# Ignition_Injection_Breakaway.net
KiCad netlist of a schematic drawn in Altium Designer
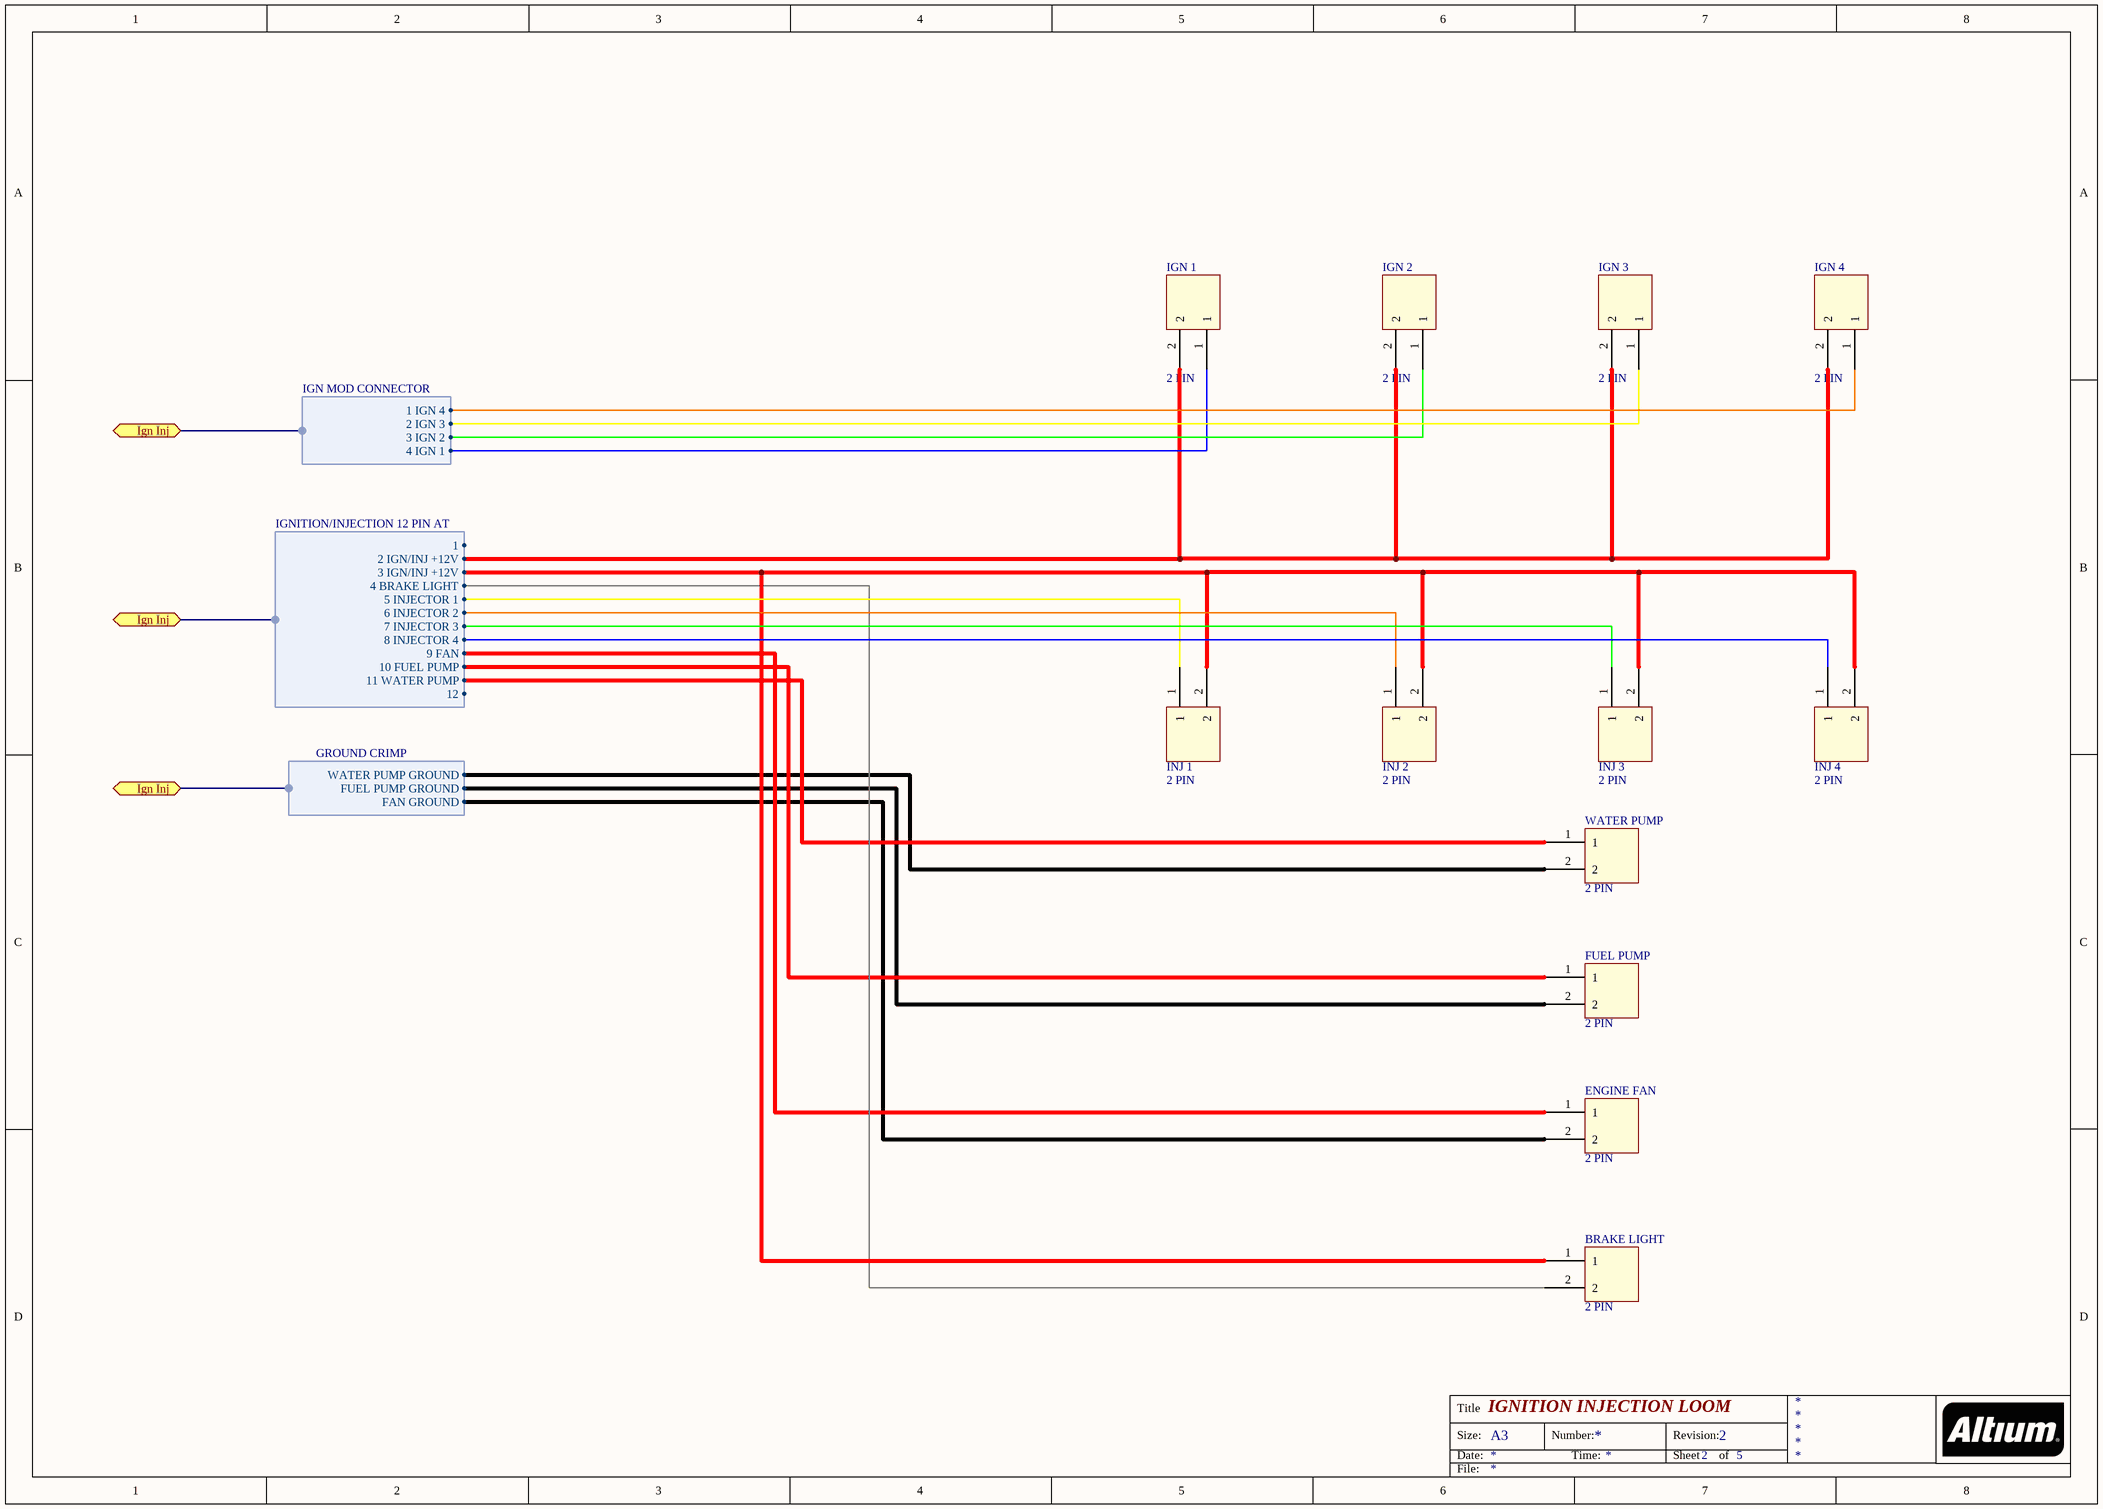
[diagram p0: Ignition Injection Breakaway.SchDoc]

(export (version "E")
  (design (tool "Eeschema 10.0.6"))
  (components
    (comp (ref "BRAKE LIGHT") (value "2 PIN") (libsource (lib "Loom Connectors") (part "2 PIN")))
    (comp (ref "ENGINE FAN") (value "2 PIN") (libsource (lib "Loom Connectors") (part "2 PIN")))
    (comp (ref "FUEL PUMP") (value "2 PIN") (libsource (lib "Loom Connectors") (part "2 PIN")))
    (comp (ref "IGN 1") (value "2 PIN") (libsource (lib "Loom Connectors") (part "2 PIN")))
    (comp (ref "IGN 2") (value "2 PIN") (libsource (lib "Loom Connectors") (part "2 PIN")))
    (comp (ref "IGN 3") (value "2 PIN") (libsource (lib "Loom Connectors") (part "2 PIN")))
    (comp (ref "IGN 4") (value "2 PIN") (libsource (lib "Loom Connectors") (part "2 PIN")))
    (comp (ref "INJ 1") (value "2 PIN") (libsource (lib "") (part "2 PIN_1")))
    (comp (ref "INJ 2") (value "2 PIN") (libsource (lib "") (part "2 PIN_1")))
    (comp (ref "INJ 3") (value "2 PIN") (libsource (lib "") (part "2 PIN_1")))
    (comp (ref "INJ 4") (value "2 PIN") (libsource (lib "") (part "2 PIN_1")))
    (comp (ref "WATER PUMP") (value "2 PIN") (libsource (lib "Loom Connectors") (part "2 PIN")))
  )
  (nets
    (net (code "2") (name "Net-(BRAKE LIGHT-Pad1)") (class "Default")
      (node (ref "BRAKE LIGHT") (pin "1") (pinfunction "1_1") (pintype "passive"))
      (node (ref "INJ 1") (pin "2") (pinfunction "2_2") (pintype "passive"))
      (node (ref "INJ 2") (pin "2") (pinfunction "2_2") (pintype "passive"))
      (node (ref "INJ 3") (pin "2") (pinfunction "2_2") (pintype "passive"))
      (node (ref "INJ 4") (pin "2") (pinfunction "2_2") (pintype "passive"))
    )
    (net (code "3") (name "Net-(IGN 1-Pad2)") (class "Default")
      (node (ref "IGN 1") (pin "2") (pinfunction "2_2") (pintype "passive"))
      (node (ref "IGN 2") (pin "2") (pinfunction "2_2") (pintype "passive"))
      (node (ref "IGN 3") (pin "2") (pinfunction "2_2") (pintype "passive"))
      (node (ref "IGN 4") (pin "2") (pinfunction "2_2") (pintype "passive"))
    )
    (net (code "4") (name "unconnected-(BRAKE LIGHT-Pad2)") (class "Default")
      (node (ref "BRAKE LIGHT") (pin "2") (pinfunction "2_2") (pintype "passive"))
    )
    (net (code "5") (name "unconnected-(ENGINE FAN-Pad1)") (class "Default")
      (node (ref "ENGINE FAN") (pin "1") (pinfunction "1_1") (pintype "passive"))
    )
    (net (code "6") (name "unconnected-(ENGINE FAN-Pad2)") (class "Default")
      (node (ref "ENGINE FAN") (pin "2") (pinfunction "2_2") (pintype "passive"))
    )
    (net (code "7") (name "unconnected-(FUEL PUMP-Pad1)") (class "Default")
      (node (ref "FUEL PUMP") (pin "1") (pinfunction "1_1") (pintype "passive"))
    )
    (net (code "8") (name "unconnected-(FUEL PUMP-Pad2)") (class "Default")
      (node (ref "FUEL PUMP") (pin "2") (pinfunction "2_2") (pintype "passive"))
    )
    (net (code "9") (name "unconnected-(IGN 1-Pad1)") (class "Default")
      (node (ref "IGN 1") (pin "1") (pinfunction "1_1") (pintype "passive"))
    )
    (net (code "10") (name "unconnected-(IGN 2-Pad1)") (class "Default")
      (node (ref "IGN 2") (pin "1") (pinfunction "1_1") (pintype "passive"))
    )
    (net (code "11") (name "unconnected-(IGN 3-Pad1)") (class "Default")
      (node (ref "IGN 3") (pin "1") (pinfunction "1_1") (pintype "passive"))
    )
    (net (code "12") (name "unconnected-(IGN 4-Pad1)") (class "Default")
      (node (ref "IGN 4") (pin "1") (pinfunction "1_1") (pintype "passive"))
    )
    (net (code "13") (name "unconnected-(INJ 1-Pad1)") (class "Default")
      (node (ref "INJ 1") (pin "1") (pinfunction "1_1") (pintype "passive"))
    )
    (net (code "14") (name "unconnected-(INJ 2-Pad1)") (class "Default")
      (node (ref "INJ 2") (pin "1") (pinfunction "1_1") (pintype "passive"))
    )
    (net (code "15") (name "unconnected-(INJ 3-Pad1)") (class "Default")
      (node (ref "INJ 3") (pin "1") (pinfunction "1_1") (pintype "passive"))
    )
    (net (code "16") (name "unconnected-(INJ 4-Pad1)") (class "Default")
      (node (ref "INJ 4") (pin "1") (pinfunction "1_1") (pintype "passive"))
    )
    (net (code "17") (name "unconnected-(WATER PUMP-Pad1)") (class "Default")
      (node (ref "WATER PUMP") (pin "1") (pinfunction "1_1") (pintype "passive"))
    )
    (net (code "18") (name "unconnected-(WATER PUMP-Pad2)") (class "Default")
      (node (ref "WATER PUMP") (pin "2") (pinfunction "2_2") (pintype "passive"))
    )
  )
)
